# sensorstation_ok.net
KiCad netlist of a schematic drawn in EAGLE
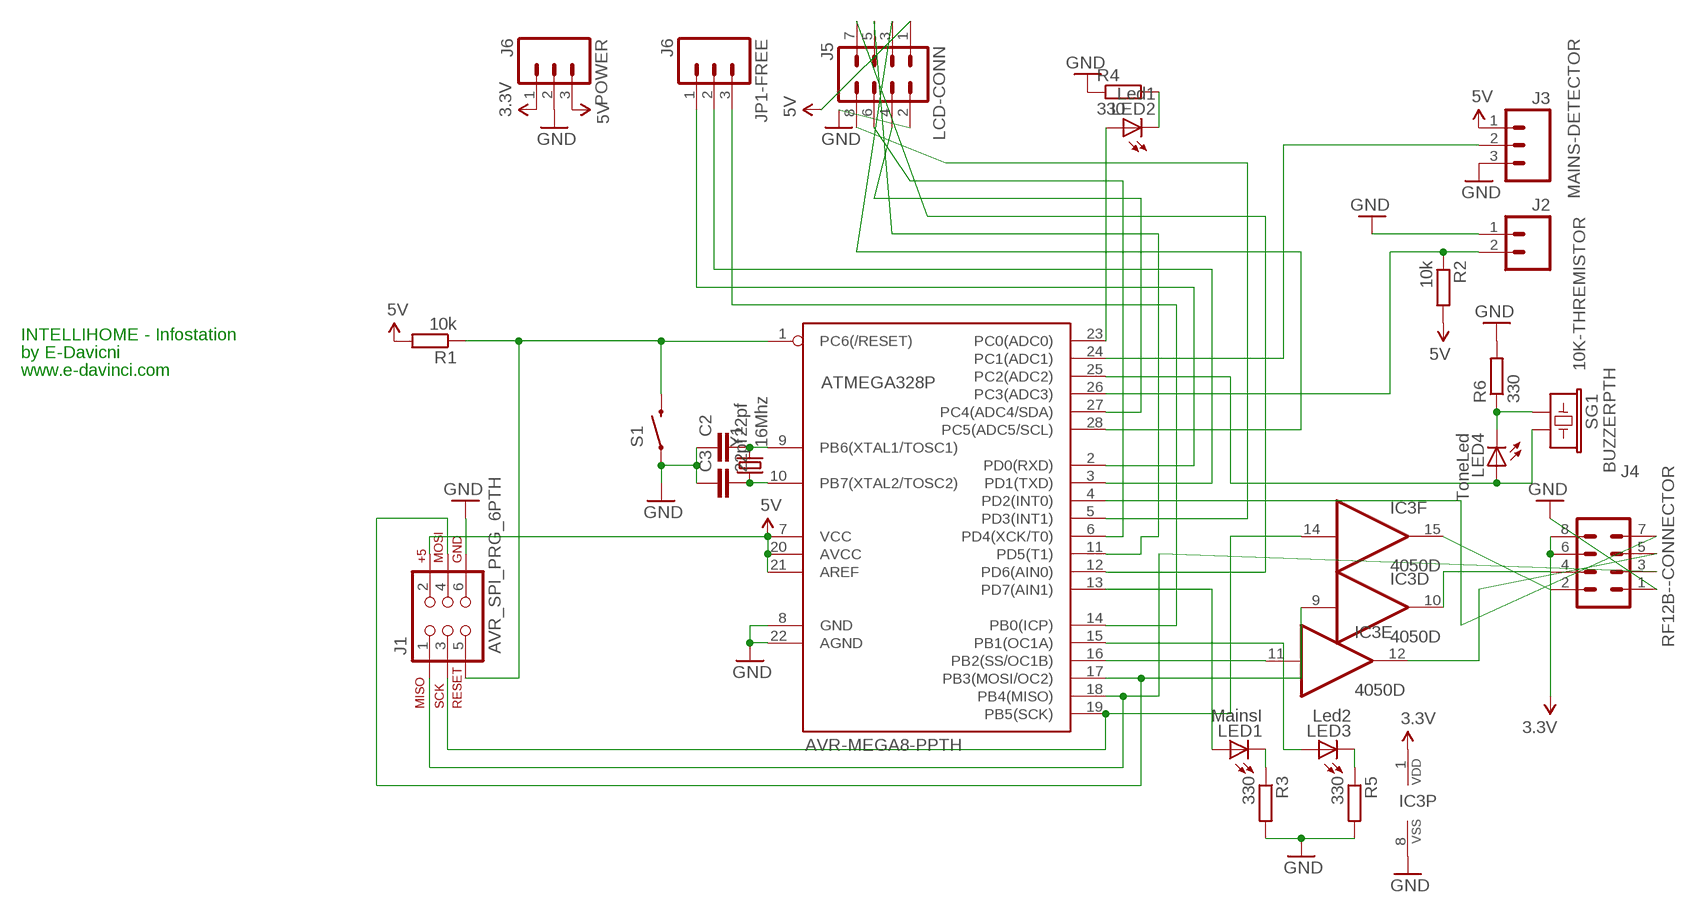
[diagram p0: schematic, sheet 1]

(export (version "E")
  (design (tool "Eeschema 10.0.6"))
  (components
    (comp (ref "10K-THREMISTOR")
      (value "J2")
      (footprint "eagle-import:1X02")
      (libsource (lib "eagle-import") (part "M02PTH"))
    )
    (comp (ref "ATMEGA328P")
      (value "AVR-MEGA8-PPTH")
      (footprint "eagle-import:DIL28-3")
      (libsource (lib "eagle-import") (part "AVR-MEGA8-PPTH"))
    )
    (comp (ref "C2")
      (value "22pf")
      (footprint "eagle-import:CAP-PTH-SMALL")
      (libsource (lib "eagle-import") (part "CAPPTH"))
    )
    (comp (ref "C3")
      (value "22pf")
      (footprint "eagle-import:CAP-PTH-SMALL")
      (libsource (lib "eagle-import") (part "CAPPTH"))
    )
    (comp (ref "IC3")
      (value "4050D")
      (footprint "eagle-import:SO16")
      (libsource (lib "eagle-import") (part "4050D"))
    )
    (comp (ref "J1")
      (value "AVR_SPI_PRG_6PTH")
      (footprint "eagle-import:2X3")
      (libsource (lib "eagle-import") (part "AVR_SPI_PRG_6PTH"))
    )
    (comp (ref "JP1-FREE")
      (value "J6")
      (footprint "eagle-import:1X03")
      (libsource (lib "eagle-import") (part "M03PTH"))
    )
    (comp (ref "LCD-CONN")
      (value "J5")
      (footprint "eagle-import:2X4")
      (libsource (lib "eagle-import") (part "M04X2"))
    )
    (comp (ref "LED1")
      (value "MainsI")
      (footprint "eagle-import:LED3MM")
      (libsource (lib "eagle-import") (part "LED3MM"))
    )
    (comp (ref "LED2")
      (value "Led1")
      (footprint "eagle-import:LED3MM")
      (libsource (lib "eagle-import") (part "LED3MM"))
    )
    (comp (ref "LED3")
      (value "Led2")
      (footprint "eagle-import:LED3MM")
      (libsource (lib "eagle-import") (part "LED3MM"))
    )
    (comp (ref "LED4")
      (value "ToneLed")
      (footprint "eagle-import:LED3MM")
      (libsource (lib "eagle-import") (part "LED3MM"))
    )
    (comp (ref "MAINS-DETECTOR")
      (value "J3")
      (footprint "eagle-import:1X03")
      (libsource (lib "eagle-import") (part "M03PTH"))
    )
    (comp (ref "POWER")
      (value "J6")
      (footprint "eagle-import:1X03")
      (libsource (lib "eagle-import") (part "M03PTH"))
    )
    (comp (ref "R1")
      (value "10k")
      (footprint "eagle-import:0207_2V")
      (libsource (lib "eagle-import") (part "R-EU_0207/2V"))
    )
    (comp (ref "R2")
      (value "10k")
      (footprint "eagle-import:0207_2V")
      (libsource (lib "eagle-import") (part "R-EU_0207/2V"))
    )
    (comp (ref "R3")
      (value "330")
      (footprint "eagle-import:0207_2V")
      (libsource (lib "eagle-import") (part "R-EU_0207/2V"))
    )
    (comp (ref "R4")
      (value "330")
      (footprint "eagle-import:0207_2V")
      (libsource (lib "eagle-import") (part "R-EU_0207/2V"))
    )
    (comp (ref "R5")
      (value "330")
      (footprint "eagle-import:0207_2V")
      (libsource (lib "eagle-import") (part "R-EU_0207/2V"))
    )
    (comp (ref "R6")
      (value "330")
      (footprint "eagle-import:0207_2V")
      (libsource (lib "eagle-import") (part "R-EU_0207/2V"))
    )
    (comp (ref "RF12B--CONNECTOR")
      (value "J4")
      (footprint "eagle-import:2X4")
      (libsource (lib "eagle-import") (part "M04X2"))
    )
    (comp (ref "S1")
      (value "SWITCH-MOMENTARY-2PTH")
      (footprint "eagle-import:TACTILE-PTH")
      (libsource (lib "eagle-import") (part "SWITCH-MOMENTARY-2PTH"))
    )
    (comp (ref "SG1")
      (value "BUZZERPTH")
      (footprint "eagle-import:BUZZER-12MM")
      (libsource (lib "eagle-import") (part "BUZZERPTH"))
    )
    (comp (ref "Y1")
      (value "16Mhz")
      (footprint "eagle-import:HC49US")
      (libsource (lib "eagle-import") (part "CRYSTALHC49US"))
    )
  )
  (nets
    (net (code "1") (name "3.3V") (class "Default")
      (node (ref "IC3") (pin "1") (pinfunction "VDD_1") (pintype "power_in"))
      (node (ref "POWER") (pin "1") (pinfunction "1_1") (pintype "passive"))
      (node (ref "RF12B--CONNECTOR") (pin "6") (pinfunction "6_6") (pintype "passive"))
      (node (ref "RF12B--CONNECTOR") (pin "8") (pinfunction "8_8") (pintype "passive"))
    )
    (net (code "2") (name "5V") (class "Default")
      (node (ref "ATMEGA328P") (pin "20") (pinfunction "AVCC_20") (pintype "bidirectional"))
      (node (ref "ATMEGA328P") (pin "21") (pinfunction "AREF_21") (pintype "bidirectional"))
      (node (ref "ATMEGA328P") (pin "7") (pinfunction "VCC_7") (pintype "bidirectional"))
      (node (ref "J1") (pin "2") (pinfunction "2_2") (pintype "passive"))
      (node (ref "LCD-CONN") (pin "1") (pinfunction "1_1") (pintype "passive"))
      (node (ref "MAINS-DETECTOR") (pin "1") (pinfunction "1_1") (pintype "passive"))
      (node (ref "POWER") (pin "3") (pinfunction "3_3") (pintype "passive"))
      (node (ref "R1") (pin "2") (pinfunction "2_2") (pintype "passive"))
      (node (ref "R2") (pin "2") (pinfunction "2_2") (pintype "passive"))
    )
    (net (code "3") (name "GND") (class "Default")
      (node (ref "10K-THREMISTOR") (pin "1") (pinfunction "1_1") (pintype "passive"))
      (node (ref "ATMEGA328P") (pin "22") (pinfunction "AGND_22") (pintype "bidirectional"))
      (node (ref "ATMEGA328P") (pin "8") (pinfunction "GND_8") (pintype "bidirectional"))
      (node (ref "C2") (pin "1") (pinfunction "1_1") (pintype "passive"))
      (node (ref "C3") (pin "1") (pinfunction "1_1") (pintype "passive"))
      (node (ref "IC3") (pin "8") (pinfunction "VSS_8") (pintype "power_in"))
      (node (ref "J1") (pin "6") (pinfunction "6_6") (pintype "passive"))
      (node (ref "LCD-CONN") (pin "2") (pinfunction "2_2") (pintype "passive"))
      (node (ref "MAINS-DETECTOR") (pin "3") (pinfunction "3_3") (pintype "passive"))
      (node (ref "POWER") (pin "2") (pinfunction "2_2") (pintype "passive"))
      (node (ref "R3") (pin "2") (pinfunction "2_2") (pintype "passive"))
      (node (ref "R4") (pin "1") (pinfunction "1_1") (pintype "passive"))
      (node (ref "R5") (pin "2") (pinfunction "2_2") (pintype "passive"))
      (node (ref "R6") (pin "2") (pinfunction "2_2") (pintype "passive"))
      (node (ref "RF12B--CONNECTOR") (pin "1") (pinfunction "1_1") (pintype "passive"))
      (node (ref "S1") (pin "1") (pinfunction "1_1") (pintype "passive"))
    )
    (net (code "4") (name "Net-(ATMEGA328P-PB0(ICP))") (class "Default")
      (node (ref "ATMEGA328P") (pin "14") (pinfunction "PB0(ICP)_14") (pintype "bidirectional"))
      (node (ref "JP1-FREE") (pin "3") (pinfunction "3_3") (pintype "passive"))
    )
    (net (code "5") (name "Net-(ATMEGA328P-PB1(OC1A))") (class "Default")
      (node (ref "ATMEGA328P") (pin "15") (pinfunction "PB1(OC1A)_15") (pintype "bidirectional"))
      (node (ref "LED3") (pin "A") (pinfunction "A_A") (pintype "passive"))
    )
    (net (code "6") (name "Net-(ATMEGA328P-PB2(SS{slash}OC1B))") (class "Default")
      (node (ref "ATMEGA328P") (pin "16") (pinfunction "PB2(SS/OC1B)_16") (pintype "bidirectional"))
      (node (ref "IC3") (pin "11") (pinfunction "I_11") (pintype "input"))
    )
    (net (code "7") (name "Net-(ATMEGA328P-PB3(MOSI{slash}OC2))") (class "Default")
      (node (ref "ATMEGA328P") (pin "17") (pinfunction "PB3(MOSI/OC2)_17") (pintype "bidirectional"))
      (node (ref "IC3") (pin "9") (pinfunction "I_9") (pintype "input"))
      (node (ref "J1") (pin "4") (pinfunction "4_4") (pintype "passive"))
    )
    (net (code "8") (name "Net-(ATMEGA328P-PB4(MISO))") (class "Default")
      (node (ref "ATMEGA328P") (pin "18") (pinfunction "PB4(MISO)_18") (pintype "bidirectional"))
      (node (ref "J1") (pin "1") (pinfunction "1_1") (pintype "passive"))
      (node (ref "RF12B--CONNECTOR") (pin "3") (pinfunction "3_3") (pintype "passive"))
    )
    (net (code "9") (name "Net-(ATMEGA328P-PB5(SCK))") (class "Default")
      (node (ref "ATMEGA328P") (pin "19") (pinfunction "PB5(SCK)_19") (pintype "bidirectional"))
      (node (ref "IC3") (pin "14") (pinfunction "I_14") (pintype "input"))
      (node (ref "J1") (pin "3") (pinfunction "3_3") (pintype "passive"))
    )
    (net (code "10") (name "Net-(ATMEGA328P-PB6(XTAL1{slash}TOSC1))") (class "Default")
      (node (ref "ATMEGA328P") (pin "9") (pinfunction "PB6(XTAL1/TOSC1)_9") (pintype "bidirectional"))
      (node (ref "C2") (pin "2") (pinfunction "2_2") (pintype "passive"))
      (node (ref "Y1") (pin "2") (pinfunction "2_2") (pintype "passive"))
    )
    (net (code "11") (name "Net-(ATMEGA328P-PB7(XTAL2{slash}TOSC2))") (class "Default")
      (node (ref "ATMEGA328P") (pin "10") (pinfunction "PB7(XTAL2/TOSC2)_10") (pintype "bidirectional"))
      (node (ref "C3") (pin "2") (pinfunction "2_2") (pintype "passive"))
      (node (ref "Y1") (pin "1") (pinfunction "1_1") (pintype "passive"))
    )
    (net (code "12") (name "Net-(ATMEGA328P-PC0(ADC0))") (class "Default")
      (node (ref "ATMEGA328P") (pin "23") (pinfunction "PC0(ADC0)_23") (pintype "bidirectional"))
      (node (ref "LED2") (pin "A") (pinfunction "A_A") (pintype "passive"))
    )
    (net (code "13") (name "Net-(ATMEGA328P-PC1(ADC1))") (class "Default")
      (node (ref "ATMEGA328P") (pin "24") (pinfunction "PC1(ADC1)_24") (pintype "bidirectional"))
      (node (ref "MAINS-DETECTOR") (pin "2") (pinfunction "2_2") (pintype "passive"))
    )
    (net (code "14") (name "Net-(ATMEGA328P-PC2(ADC2))") (class "Default")
      (node (ref "ATMEGA328P") (pin "25") (pinfunction "PC2(ADC2)_25") (pintype "bidirectional"))
      (node (ref "LED4") (pin "A") (pinfunction "A_A") (pintype "passive"))
      (node (ref "SG1") (pin "-") (pinfunction "2_-") (pintype "passive"))
    )
    (net (code "15") (name "Net-(ATMEGA328P-PC3(ADC3))") (class "Default")
      (node (ref "10K-THREMISTOR") (pin "2") (pinfunction "2_2") (pintype "passive"))
      (node (ref "ATMEGA328P") (pin "26") (pinfunction "PC3(ADC3)_26") (pintype "bidirectional"))
      (node (ref "R2") (pin "1") (pinfunction "1_1") (pintype "passive"))
    )
    (net (code "16") (name "Net-(ATMEGA328P-PC4(ADC4{slash}SDA))") (class "Default")
      (node (ref "ATMEGA328P") (pin "27") (pinfunction "PC4(ADC4/SDA)_27") (pintype "bidirectional"))
      (node (ref "LCD-CONN") (pin "4") (pinfunction "4_4") (pintype "passive"))
    )
    (net (code "17") (name "Net-(ATMEGA328P-PC5(ADC5{slash}SCL))") (class "Default")
      (node (ref "ATMEGA328P") (pin "28") (pinfunction "PC5(ADC5/SCL)_28") (pintype "bidirectional"))
      (node (ref "LCD-CONN") (pin "3") (pinfunction "3_3") (pintype "passive"))
    )
    (net (code "18") (name "Net-(ATMEGA328P-PC6({slash}RESET))") (class "Default")
      (node (ref "ATMEGA328P") (pin "1") (pinfunction "PC6(/RESET)_1") (pintype "bidirectional"))
      (node (ref "J1") (pin "5") (pinfunction "5_5") (pintype "passive"))
      (node (ref "R1") (pin "1") (pinfunction "1_1") (pintype "passive"))
      (node (ref "S1") (pin "3") (pinfunction "2_3") (pintype "passive"))
    )
    (net (code "19") (name "Net-(ATMEGA328P-PD0(RXD))") (class "Default")
      (node (ref "ATMEGA328P") (pin "2") (pinfunction "PD0(RXD)_2") (pintype "bidirectional"))
      (node (ref "JP1-FREE") (pin "1") (pinfunction "1_1") (pintype "passive"))
    )
    (net (code "20") (name "Net-(ATMEGA328P-PD1(TXD))") (class "Default")
      (node (ref "ATMEGA328P") (pin "3") (pinfunction "PD1(TXD)_3") (pintype "bidirectional"))
      (node (ref "JP1-FREE") (pin "2") (pinfunction "2_2") (pintype "passive"))
    )
    (net (code "21") (name "Net-(ATMEGA328P-PD2(INT0))") (class "Default")
      (node (ref "ATMEGA328P") (pin "4") (pinfunction "PD2(INT0)_4") (pintype "bidirectional"))
      (node (ref "RF12B--CONNECTOR") (pin "7") (pinfunction "7_7") (pintype "passive"))
    )
    (net (code "22") (name "Net-(ATMEGA328P-PD3(INT1))") (class "Default")
      (node (ref "ATMEGA328P") (pin "5") (pinfunction "PD3(INT1)_5") (pintype "bidirectional"))
      (node (ref "LCD-CONN") (pin "8") (pinfunction "8_8") (pintype "passive"))
    )
    (net (code "23") (name "Net-(ATMEGA328P-PD4(XCK{slash}T0))") (class "Default")
      (node (ref "ATMEGA328P") (pin "6") (pinfunction "PD4(XCK/T0)_6") (pintype "bidirectional"))
      (node (ref "LCD-CONN") (pin "6") (pinfunction "6_6") (pintype "passive"))
    )
    (net (code "24") (name "Net-(ATMEGA328P-PD5(T1))") (class "Default")
      (node (ref "ATMEGA328P") (pin "11") (pinfunction "PD5(T1)_11") (pintype "bidirectional"))
      (node (ref "LCD-CONN") (pin "5") (pinfunction "5_5") (pintype "passive"))
    )
    (net (code "25") (name "Net-(ATMEGA328P-PD6(AIN0))") (class "Default")
      (node (ref "ATMEGA328P") (pin "12") (pinfunction "PD6(AIN0)_12") (pintype "bidirectional"))
      (node (ref "LCD-CONN") (pin "7") (pinfunction "7_7") (pintype "passive"))
    )
    (net (code "26") (name "Net-(ATMEGA328P-PD7(AIN1))") (class "Default")
      (node (ref "ATMEGA328P") (pin "13") (pinfunction "PD7(AIN1)_13") (pintype "bidirectional"))
      (node (ref "LED1") (pin "A") (pinfunction "A_A") (pintype "passive"))
    )
    (net (code "27") (name "Net-(IC3D-O)") (class "Default")
      (node (ref "IC3") (pin "10") (pinfunction "O_10") (pintype "output"))
      (node (ref "RF12B--CONNECTOR") (pin "4") (pinfunction "4_4") (pintype "passive"))
    )
    (net (code "28") (name "Net-(IC3E-O)") (class "Default")
      (node (ref "IC3") (pin "12") (pinfunction "O_12") (pintype "output"))
      (node (ref "RF12B--CONNECTOR") (pin "5") (pinfunction "5_5") (pintype "passive"))
    )
    (net (code "29") (name "Net-(IC3F-O)") (class "Default")
      (node (ref "IC3") (pin "15") (pinfunction "O_15") (pintype "output"))
      (node (ref "RF12B--CONNECTOR") (pin "2") (pinfunction "2_2") (pintype "passive"))
    )
    (net (code "30") (name "Net-(LED1-C)") (class "Default")
      (node (ref "LED1") (pin "K") (pinfunction "C_K") (pintype "passive"))
      (node (ref "R3") (pin "1") (pinfunction "1_1") (pintype "passive"))
    )
    (net (code "31") (name "Net-(LED2-C)") (class "Default")
      (node (ref "LED2") (pin "K") (pinfunction "C_K") (pintype "passive"))
      (node (ref "R4") (pin "2") (pinfunction "2_2") (pintype "passive"))
    )
    (net (code "32") (name "Net-(LED3-C)") (class "Default")
      (node (ref "LED3") (pin "K") (pinfunction "C_K") (pintype "passive"))
      (node (ref "R5") (pin "1") (pinfunction "1_1") (pintype "passive"))
    )
    (net (code "33") (name "Net-(LED4-C)") (class "Default")
      (node (ref "LED4") (pin "K") (pinfunction "C_K") (pintype "passive"))
      (node (ref "R6") (pin "1") (pinfunction "1_1") (pintype "passive"))
      (node (ref "SG1") (pin "+") (pinfunction "1_+") (pintype "passive"))
    )
  )
)
